# Active_Indicator.net
KiCad netlist of a schematic drawn in Altium Designer
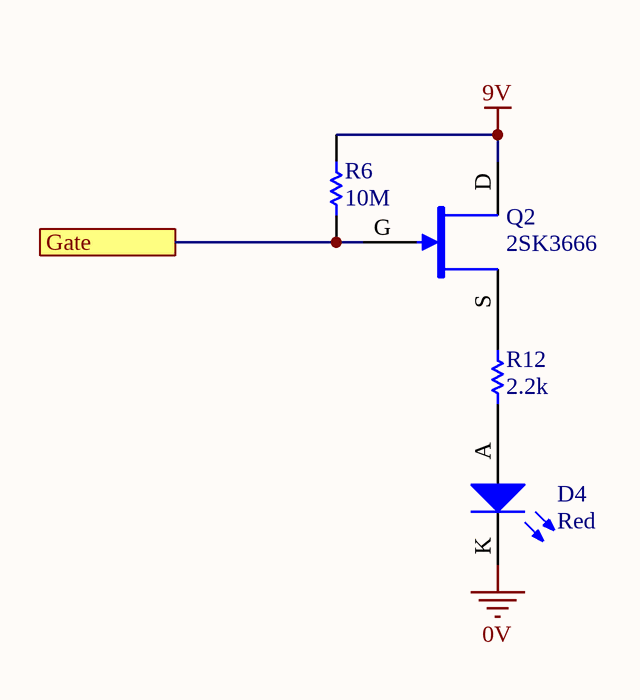
[diagram p0: Active Indicator.SchDoc]

(export (version "E")
  (design (tool "Eeschema 10.0.6"))
  (components
    (comp (ref "D4")
      (value "Red")
      (footprint "0805 LED")
      (description "Red LED Indication - Discrete 1.75V 0805 (2012 Metric)")
      (fields (field (name "PART NUMBER") "SML-210LTT86") (field (name "MANUFACTURER") "ROHM Semiconductor"))
      (libsource (lib "ts_20-standard-library") (part "LED"))
    )
    (comp (ref "Q2")
      (value "2SK3666")
      (footprint "ON SOT-23 JFET")
      (description "JFET N-Channel 10mA 200mW Surface Mount 3-CP")
      (fields
        (field (name "MANUFACTURER") "ON Semiconductor")
        (field (name "DIGIKEY PART NUMBER") "869-1107-1-ND")
        (field (name "PUBLISHER") "Altium Limited")
      )
      (libsource (lib "ts_20-standard-library") (part "JFET-N"))
    )
    (comp (ref "R6")
      (value "10M")
      (footprint "0805")
      (fields
        (field (name "PART NUMBER") "RC0805FR0710ML")
        (field (name "MANUFACTURER") "YAGEO")
        (field (name "TOLERANCE") "0.01")
      )
      (libsource (lib "ts_20-standard-library") (part "Resistor"))
    )
    (comp (ref "R12")
      (value "2.2k")
      (footprint "0805")
      (fields
        (field (name "PART NUMBER") "RC0805FR072K2L")
        (field (name "MANUFACTURER") "YAGEO")
        (field (name "TOLERANCE") "0.01")
      )
      (libsource (lib "ts_20-standard-library") (part "Resistor"))
    )
  )
  (nets
    (net (code "1") (name "/Gate") (class "Default")
      (node (ref "Q2") (pin "G") (pinfunction "G_G") (pintype "passive"))
      (node (ref "R6") (pin "1") (pinfunction "1_1") (pintype "passive"))
    )
    (net (code "2") (name "0V") (class "Default")
      (node (ref "D4") (pin "K") (pinfunction "K_K") (pintype "passive"))
    )
    (net (code "3") (name "9V") (class "Default")
      (node (ref "Q2") (pin "D") (pinfunction "D_D") (pintype "passive"))
      (node (ref "R6") (pin "2") (pinfunction "2_2") (pintype "passive"))
    )
    (net (code "4") (name "Net-(D4-PadA)") (class "Default")
      (node (ref "D4") (pin "A") (pinfunction "A_A") (pintype "passive"))
      (node (ref "R12") (pin "1") (pinfunction "1_1") (pintype "passive"))
    )
    (net (code "5") (name "Net-(Q2-PadS)") (class "Default")
      (node (ref "Q2") (pin "S") (pinfunction "S_S") (pintype "passive"))
      (node (ref "R12") (pin "2") (pinfunction "2_2") (pintype "passive"))
    )
  )
)
